# FPGA_Power_Ports.net
KiCad netlist of a schematic drawn in Altium Designer
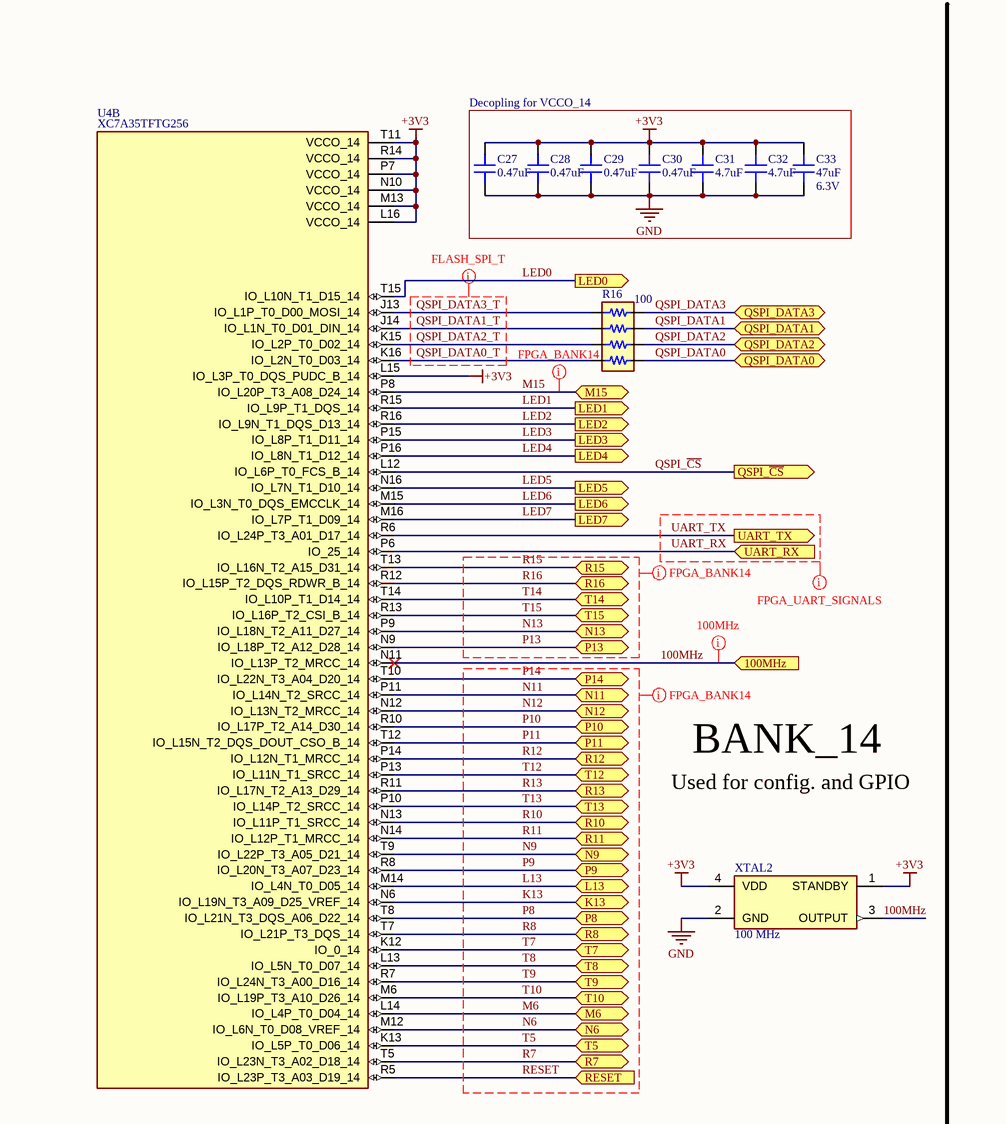
[diagram p0: FPGA_Power&Ports.SchDoc, top left]
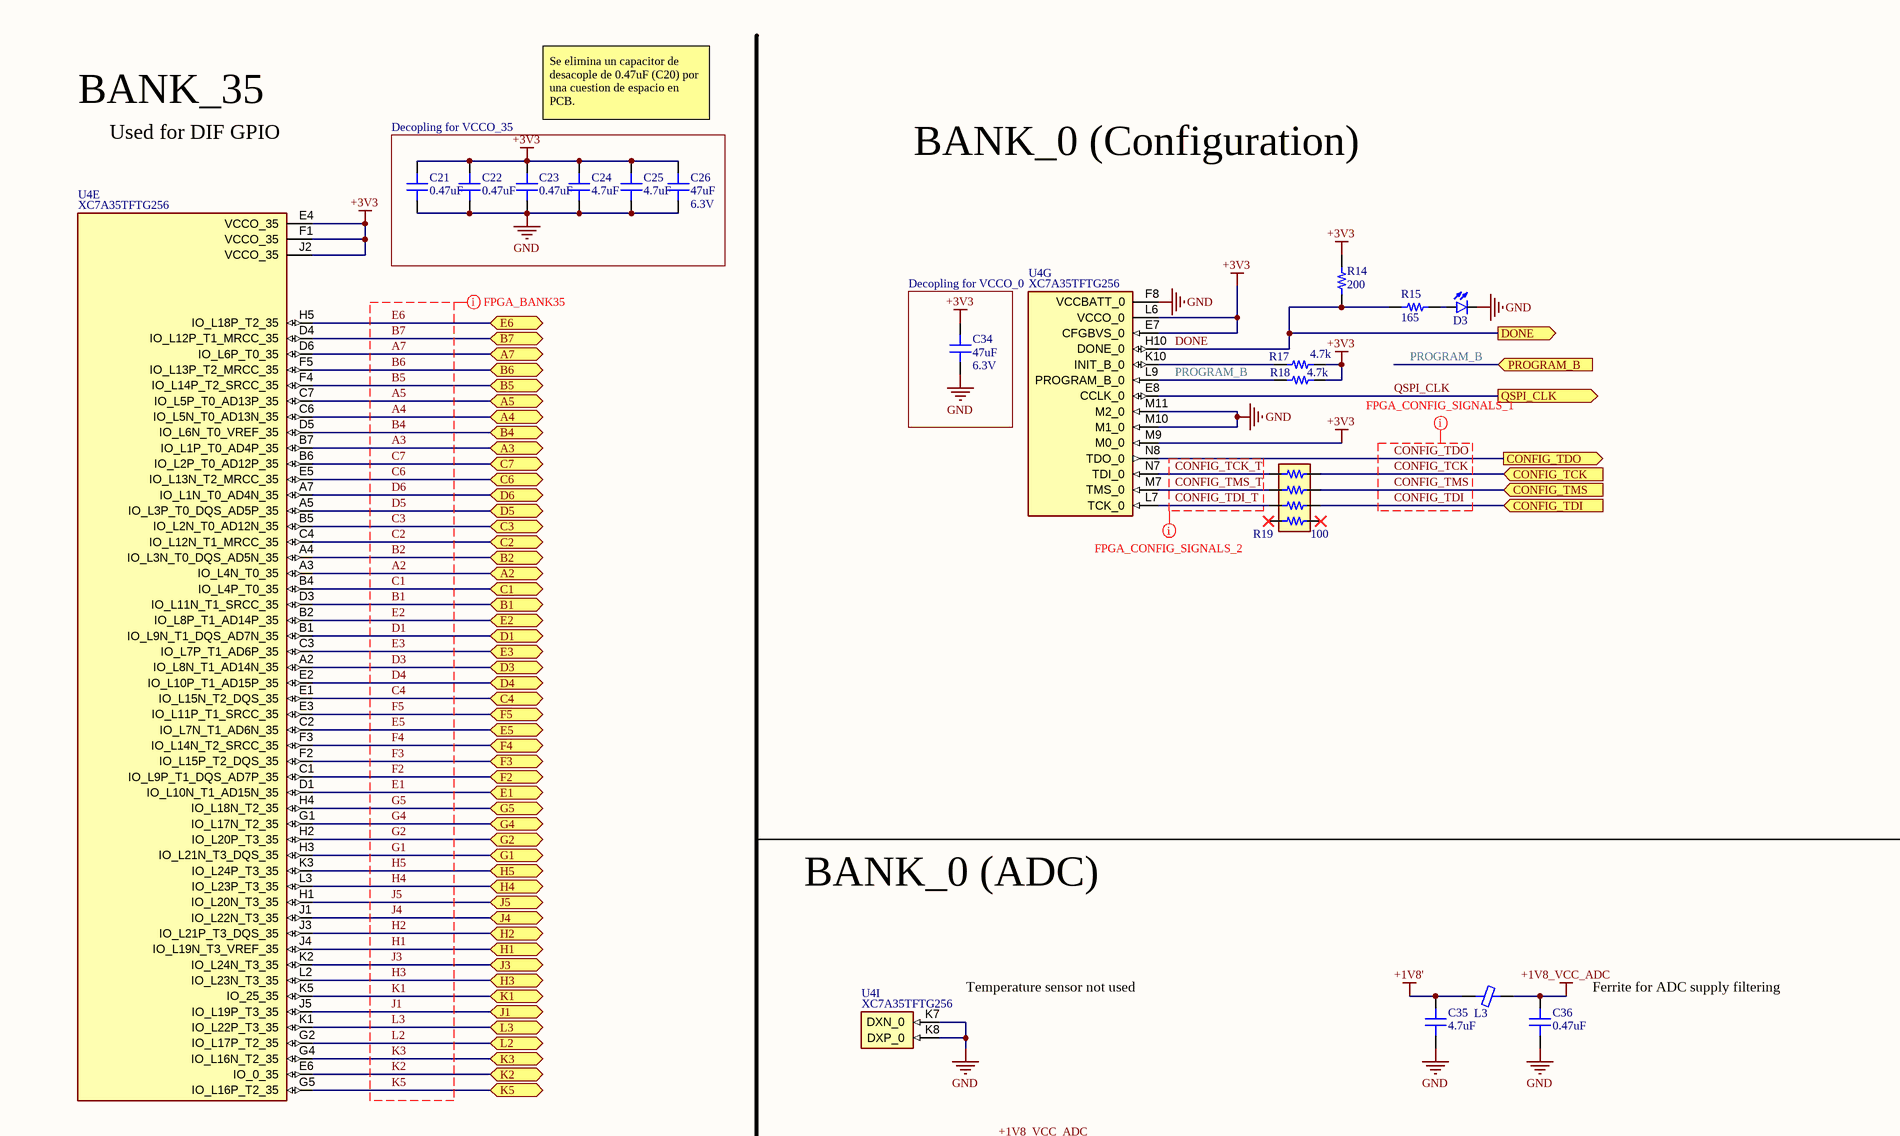
[diagram p1: FPGA_Power&Ports.SchDoc, top right]
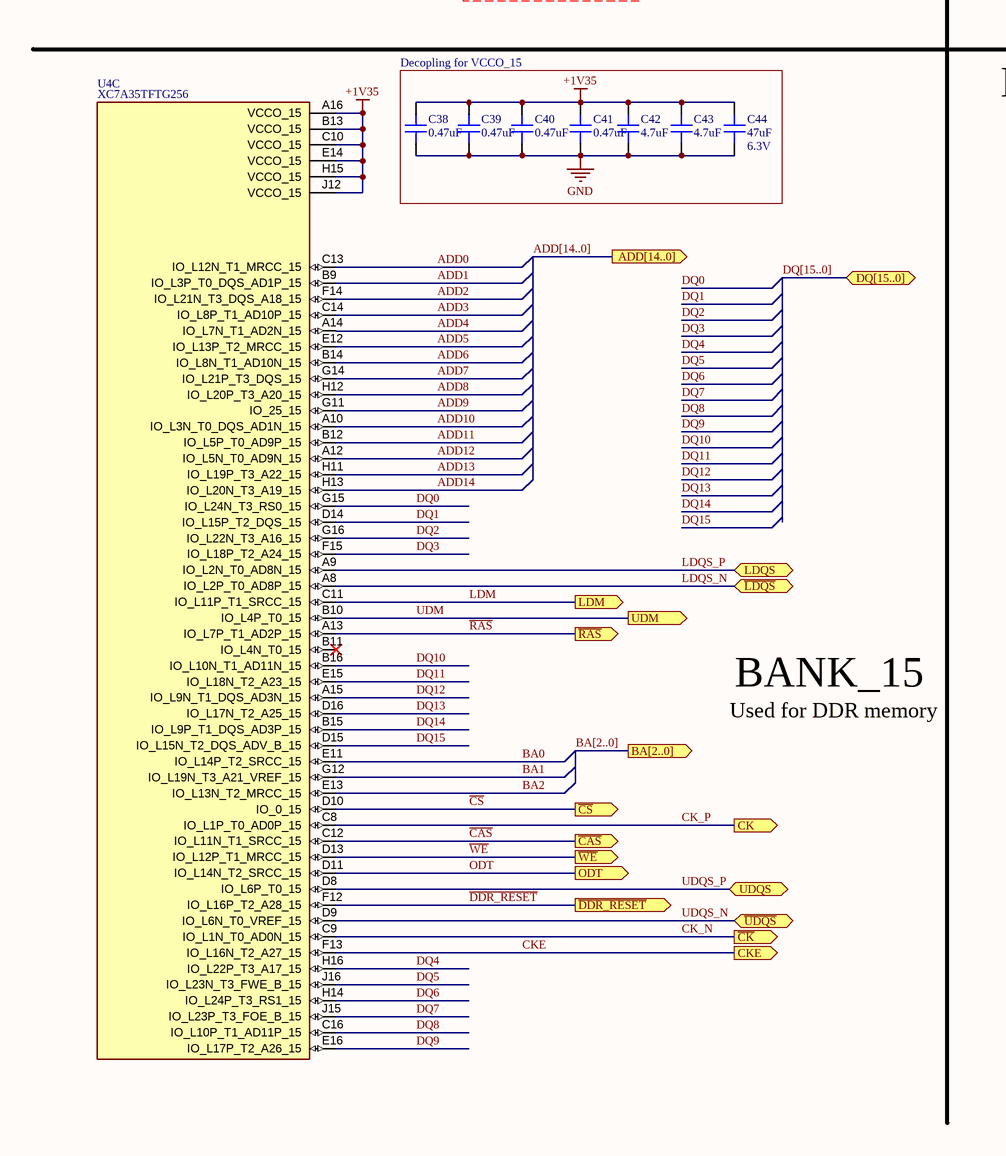
[diagram p2: FPGA_Power&Ports.SchDoc, bottom left]
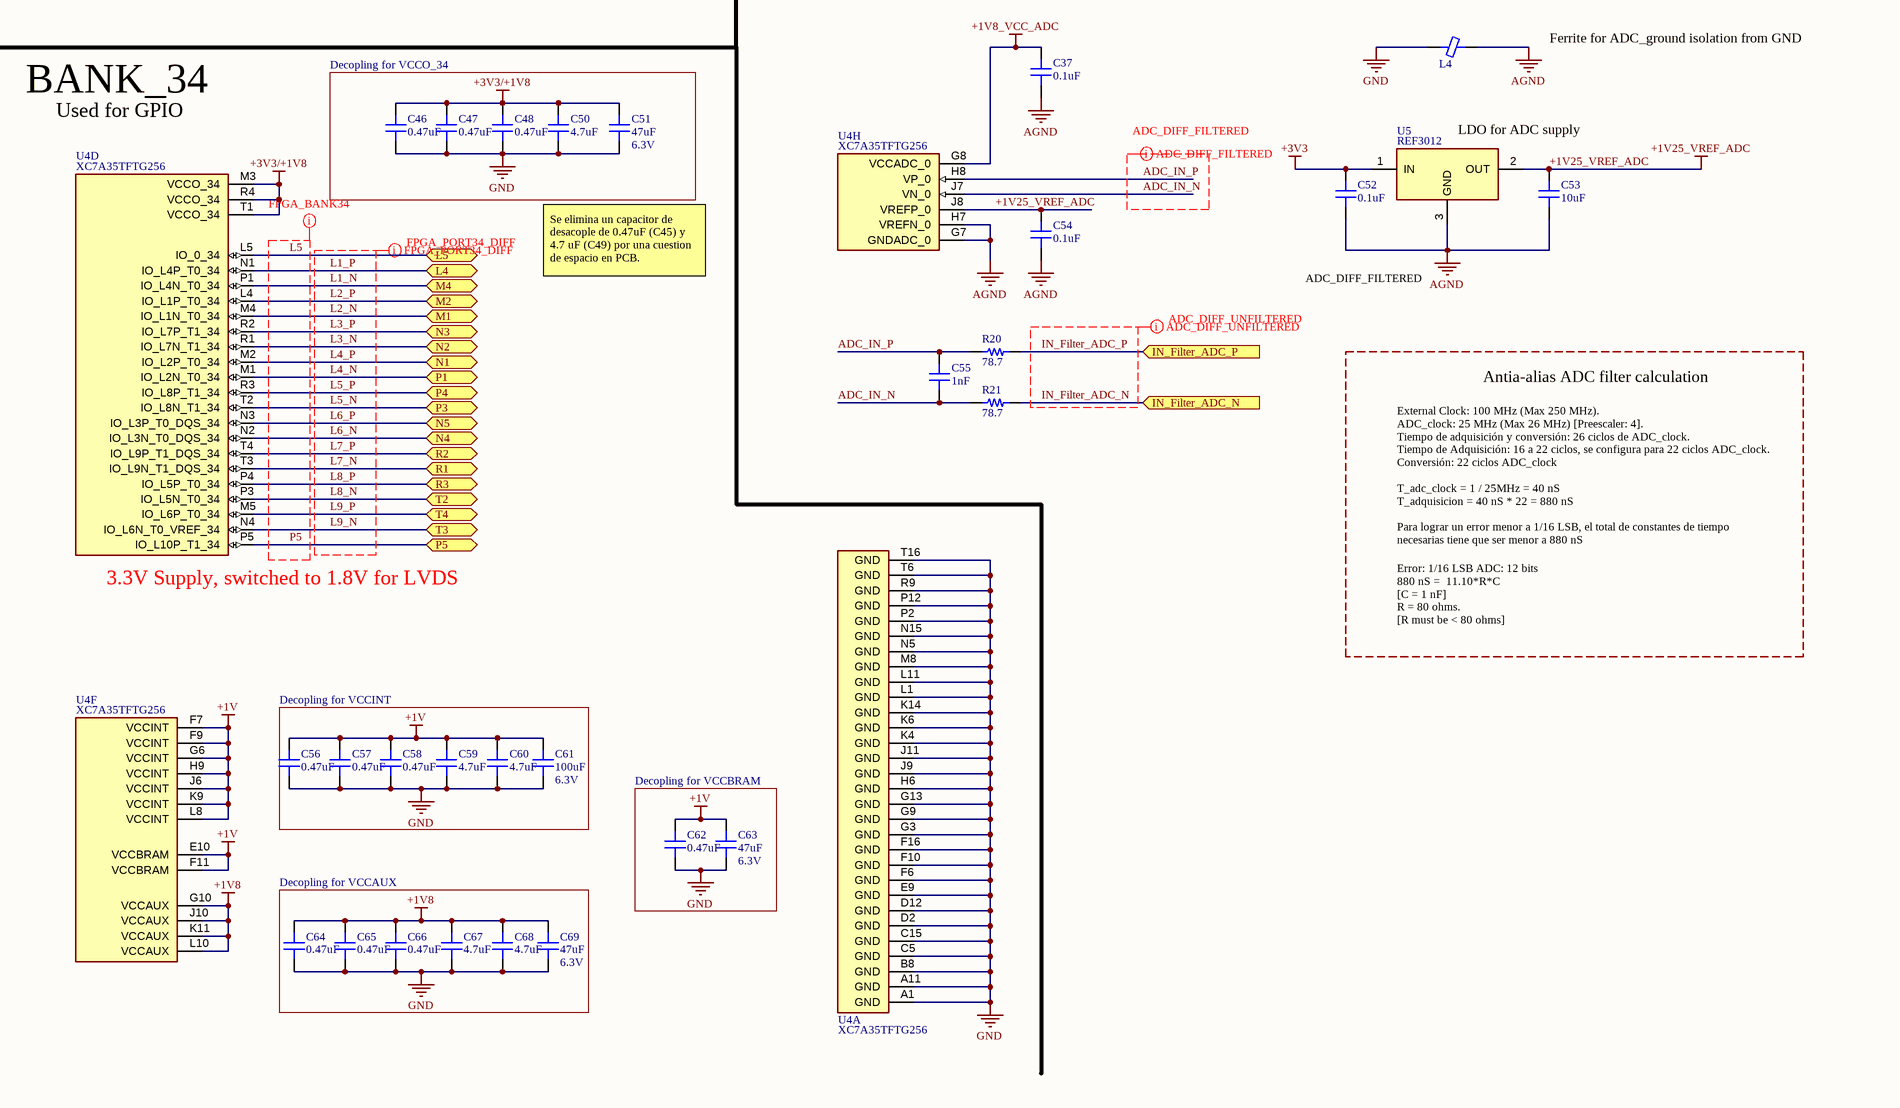
[diagram p3: FPGA_Power&Ports.SchDoc, bottom right]

(export (version "E")
  (design (tool "Eeschema 10.0.6"))
  (components
    (comp (ref "C21")
      (value "0.47uF")
      (footprint "CAP0402")
      (description "CAP CER 0.47uF 10V X7R 0402 10%")
      (fields (field (name "PARTNUMBER") "C0603C474K4RAC") (field (name "TOLERANCE") "10%"))
      (libsource (lib "Pasivos") (part "C0402C474K8RAC"))
    )
    (comp (ref "C22")
      (value "0.47uF")
      (footprint "CAP0402")
      (description "CAP CER 0.47uF 10V X7R 0402 10%")
      (fields (field (name "PARTNUMBER") "C0603C474K4RAC") (field (name "TOLERANCE") "10%"))
      (libsource (lib "Pasivos") (part "C0402C474K8RAC"))
    )
    (comp (ref "C23")
      (value "0.47uF")
      (footprint "CAP0402")
      (description "CAP CER 0.47uF 10V X7R 0402 10%")
      (fields (field (name "PARTNUMBER") "C0603C474K4RAC") (field (name "TOLERANCE") "10%"))
      (libsource (lib "Pasivos") (part "C0402C474K8RAC"))
    )
    (comp (ref "C24")
      (value "4.7uF")
      (footprint "CAP0402")
      (description "CAP CER 4.7uF 6.3V X5R 0402 10%")
      (fields (field (name "PARTNUMBER") "C0402C475M9PAC") (field (name "TOLERANCE") "10%"))
      (libsource (lib "Pasivos") (part "C0402C475M9PAC"))
    )
    (comp (ref "C25")
      (value "4.7uF")
      (footprint "CAP0402")
      (description "CAP CER 4.7uF 6.3V X5R 0402 10%")
      (fields (field (name "PARTNUMBER") "C0402C475M9PAC") (field (name "TOLERANCE") "10%"))
      (libsource (lib "Pasivos") (part "C0402C475M9PAC"))
    )
    (comp (ref "C26")
      (value "47uF")
      (footprint "CAP0805")
      (description "CAP CER 47uF 6.3V X5R 0805 20%")
      (fields
        (field (name "VOLTAGE") "6.3V")
        (field (name "MANUFACTURER") "Samsung")
        (field (name "TOLERANCE") "20%")
      )
      (libsource (lib "Pasivos") (part "CL21A476MQYNNNE"))
    )
    (comp (ref "C27")
      (value "0.47uF")
      (footprint "CAP0402")
      (description "CAP CER 0.47uF 10V X7R 0402 10%")
      (fields (field (name "PARTNUMBER") "C0603C474K4RAC") (field (name "TOLERANCE") "10%"))
      (libsource (lib "Pasivos") (part "C0402C474K8RAC"))
    )
    (comp (ref "C28")
      (value "0.47uF")
      (footprint "CAP0402")
      (description "CAP CER 0.47uF 10V X7R 0402 10%")
      (fields (field (name "PARTNUMBER") "C0603C474K4RAC") (field (name "TOLERANCE") "10%"))
      (libsource (lib "Pasivos") (part "C0402C474K8RAC"))
    )
    (comp (ref "C29")
      (value "0.47uF")
      (footprint "CAP0402")
      (description "CAP CER 0.47uF 10V X7R 0402 10%")
      (fields (field (name "PARTNUMBER") "C0603C474K4RAC") (field (name "TOLERANCE") "10%"))
      (libsource (lib "Pasivos") (part "C0402C474K8RAC"))
    )
    (comp (ref "C30")
      (value "0.47uF")
      (footprint "CAP0402")
      (description "CAP CER 0.47uF 10V X7R 0402 10%")
      (fields (field (name "PARTNUMBER") "C0603C474K4RAC") (field (name "TOLERANCE") "10%"))
      (libsource (lib "Pasivos") (part "C0402C474K8RAC"))
    )
    (comp (ref "C31")
      (value "4.7uF")
      (footprint "CAP0402")
      (description "CAP CER 4.7uF 6.3V X5R 0402 10%")
      (fields (field (name "PARTNUMBER") "C0402C475M9PAC") (field (name "TOLERANCE") "10%"))
      (libsource (lib "Pasivos") (part "C0402C475M9PAC"))
    )
    (comp (ref "C32")
      (value "4.7uF")
      (footprint "CAP0402")
      (description "CAP CER 4.7uF 6.3V X5R 0402 10%")
      (fields (field (name "PARTNUMBER") "C0402C475M9PAC") (field (name "TOLERANCE") "10%"))
      (libsource (lib "Pasivos") (part "C0402C475M9PAC"))
    )
    (comp (ref "C33")
      (value "47uF")
      (footprint "CAP0805")
      (description "CAP CER 47uF 6.3V X5R 0805 20%")
      (fields
        (field (name "VOLTAGE") "6.3V")
        (field (name "MANUFACTURER") "Samsung")
        (field (name "TOLERANCE") "20%")
      )
      (libsource (lib "Pasivos") (part "CL21A476MQYNNNE"))
    )
    (comp (ref "C34")
      (value "47uF")
      (footprint "CAP0805")
      (description "CAP CER 47uF 6.3V X5R 0805 20%")
      (fields
        (field (name "MANUFACTURER") "Samsung")
        (field (name "VOLTAGE") "6.3V")
        (field (name "TOLERANCE") "20%")
      )
      (libsource (lib "Pasivos") (part "CL21A476MQYNNNE"))
    )
    (comp (ref "C35")
      (value "4.7uF")
      (footprint "CAP0402")
      (description "CAP CER 4.7uF 6.3V X5R 0402 10%")
      (fields (field (name "PARTNUMBER") "C0402C475M9PAC") (field (name "TOLERANCE") "10%"))
      (libsource (lib "Pasivos") (part "C0402C475M9PAC"))
    )
    (comp (ref "C36")
      (value "0.47uF")
      (footprint "CAP0402")
      (description "CAP CER 0.47uF 10V X7R 0402 10%")
      (fields (field (name "PARTNUMBER") "C0603C474K4RAC") (field (name "TOLERANCE") "10%"))
      (libsource (lib "Pasivos") (part "C0402C474K8RAC"))
    )
    (comp (ref "C37")
      (value "0.1uF")
      (footprint "CAP0402")
      (description "CAP CER 0.1uF 16V X7R 0402 10%")
      (fields (field (name "TOLERANCE") "10%") (field (name "VOLTAGE") "16V"))
      (libsource (lib "Pasivos") (part "C0402C104K4RAC"))
    )
    (comp (ref "C38")
      (value "0.47uF")
      (footprint "CAP0402")
      (description "CAP CER 0.47uF 10V X7R 0402 10%")
      (fields (field (name "PARTNUMBER") "C0603C474K4RAC") (field (name "TOLERANCE") "10%"))
      (libsource (lib "Pasivos") (part "C0402C474K8RAC"))
    )
    (comp (ref "C39")
      (value "0.47uF")
      (footprint "CAP0402")
      (description "CAP CER 0.47uF 10V X7R 0402 10%")
      (fields (field (name "PARTNUMBER") "C0603C474K4RAC") (field (name "TOLERANCE") "10%"))
      (libsource (lib "Pasivos") (part "C0402C474K8RAC"))
    )
    (comp (ref "C40")
      (value "0.47uF")
      (footprint "CAP0402")
      (description "CAP CER 0.47uF 10V X7R 0402 10%")
      (fields (field (name "PARTNUMBER") "C0603C474K4RAC") (field (name "TOLERANCE") "10%"))
      (libsource (lib "Pasivos") (part "C0402C474K8RAC"))
    )
    (comp (ref "C41")
      (value "0.47uF")
      (footprint "CAP0402")
      (description "CAP CER 0.47uF 10V X7R 0402 10%")
      (fields (field (name "PARTNUMBER") "C0603C474K4RAC") (field (name "TOLERANCE") "10%"))
      (libsource (lib "Pasivos") (part "C0402C474K8RAC"))
    )
    (comp (ref "C42")
      (value "4.7uF")
      (footprint "CAP0402")
      (description "CAP CER 4.7uF 6.3V X5R 0402 10%")
      (fields (field (name "PARTNUMBER") "C0402C475M9PAC") (field (name "TOLERANCE") "10%"))
      (libsource (lib "Pasivos") (part "C0402C475M9PAC"))
    )
    (comp (ref "C43")
      (value "4.7uF")
      (footprint "CAP0402")
      (description "CAP CER 4.7uF 6.3V X5R 0402 10%")
      (fields (field (name "PARTNUMBER") "C0402C475M9PAC") (field (name "TOLERANCE") "10%"))
      (libsource (lib "Pasivos") (part "C0402C475M9PAC"))
    )
    (comp (ref "C44")
      (value "47uF")
      (footprint "CAP0805")
      (description "CAP CER 47uF 6.3V X5R 0805 20%")
      (fields
        (field (name "VOLTAGE") "6.3V")
        (field (name "MANUFACTURER") "Samsung")
        (field (name "TOLERANCE") "20%")
      )
      (libsource (lib "Pasivos") (part "CL21A476MQYNNNE"))
    )
    (comp (ref "C46")
      (value "0.47uF")
      (footprint "CAP0402")
      (description "CAP CER 0.47uF 10V X7R 0402 10%")
      (fields (field (name "PARTNUMBER") "C0603C474K4RAC") (field (name "TOLERANCE") "10%"))
      (libsource (lib "Pasivos") (part "C0402C474K8RAC"))
    )
    (comp (ref "C47")
      (value "0.47uF")
      (footprint "CAP0402")
      (description "CAP CER 0.47uF 10V X7R 0402 10%")
      (fields (field (name "PARTNUMBER") "C0603C474K4RAC") (field (name "TOLERANCE") "10%"))
      (libsource (lib "Pasivos") (part "C0402C474K8RAC"))
    )
    (comp (ref "C48")
      (value "0.47uF")
      (footprint "CAP0402")
      (description "CAP CER 0.47uF 10V X7R 0402 10%")
      (fields (field (name "PARTNUMBER") "C0603C474K4RAC") (field (name "TOLERANCE") "10%"))
      (libsource (lib "Pasivos") (part "C0402C474K8RAC"))
    )
    (comp (ref "C50")
      (value "4.7uF")
      (footprint "CAP0402")
      (description "CAP CER 4.7uF 6.3V X5R 0402 10%")
      (fields (field (name "PARTNUMBER") "C0402C475M9PAC") (field (name "TOLERANCE") "10%"))
      (libsource (lib "Pasivos") (part "C0402C475M9PAC"))
    )
    (comp (ref "C51")
      (value "47uF")
      (footprint "CAP0805")
      (description "CAP CER 47uF 6.3V X5R 0805 20%")
      (fields
        (field (name "VOLTAGE") "6.3V")
        (field (name "MANUFACTURER") "Samsung")
        (field (name "TOLERANCE") "20%")
      )
      (libsource (lib "Pasivos") (part "CL21A476MQYNNNE"))
    )
    (comp (ref "C52")
      (value "0.1uF")
      (footprint "CAP0402")
      (description "CAP CER 0.1uF 16V X7R 0402 10%")
      (fields (field (name "TOLERANCE") "10%") (field (name "VOLTAGE") "16V"))
      (libsource (lib "Pasivos") (part "C0402C104K4RAC"))
    )
    (comp (ref "C53")
      (value "10uF")
      (footprint "CAP0402")
      (description "CAP CER 10uF 6.3V X5R 0402 10%")
      (fields (field (name "TOLERANCE") "10%") (field (name "MANUFACTURER") "Kemet"))
      (libsource (lib "Pasivos") (part "C0402C106M9PAC"))
    )
    (comp (ref "C54")
      (value "0.1uF")
      (footprint "CAP0402")
      (description "CAP CER 0.1uF 16V X7R 0402 10%")
      (fields (field (name "TOLERANCE") "10%") (field (name "VOLTAGE") "16V"))
      (libsource (lib "Pasivos") (part "C0402C104K4RAC"))
    )
    (comp (ref "C55")
      (value "1nF")
      (footprint "CAP0402")
      (description "CAP CER 1nF 16V X7R 0402 10%")
      (fields (field (name "TOLERANCE") "10%") (field (name "PARTNUMBER") "C0402C102K4RAC"))
      (libsource (lib "Pasivos") (part "C0402C102K4RAC"))
    )
    (comp (ref "C56")
      (value "0.47uF")
      (footprint "CAP0402")
      (description "CAP CER 0.47uF 10V X7R 0402 10%")
      (fields (field (name "PARTNUMBER") "C0603C474K4RAC") (field (name "TOLERANCE") "10%"))
      (libsource (lib "Pasivos") (part "C0402C474K8RAC"))
    )
    (comp (ref "C57")
      (value "0.47uF")
      (footprint "CAP0402")
      (description "CAP CER 0.47uF 10V X7R 0402 10%")
      (fields (field (name "PARTNUMBER") "C0603C474K4RAC") (field (name "TOLERANCE") "10%"))
      (libsource (lib "Pasivos") (part "C0402C474K8RAC"))
    )
    (comp (ref "C58")
      (value "0.47uF")
      (footprint "CAP0402")
      (description "CAP CER 0.47uF 10V X7R 0402 10%")
      (fields (field (name "PARTNUMBER") "C0603C474K4RAC") (field (name "TOLERANCE") "10%"))
      (libsource (lib "Pasivos") (part "C0402C474K8RAC"))
    )
    (comp (ref "C59")
      (value "4.7uF")
      (footprint "CAP0402")
      (description "CAP CER 4.7uF 6.3V X5R 0402 10%")
      (fields (field (name "PARTNUMBER") "C0402C475M9PAC") (field (name "TOLERANCE") "10%"))
      (libsource (lib "Pasivos") (part "C0402C475M9PAC"))
    )
    (comp (ref "C60")
      (value "4.7uF")
      (footprint "CAP0402")
      (description "CAP CER 4.7uF 6.3V X5R 0402 10%")
      (fields (field (name "PARTNUMBER") "C0402C475M9PAC") (field (name "TOLERANCE") "10%"))
      (libsource (lib "Pasivos") (part "C0402C475M9PAC"))
    )
    (comp (ref "C61")
      (value "100uF")
      (footprint "CAP1206")
      (description "CAP CER 100uF 6.3V X5R 1206 20%")
      (fields
        (field (name "PARTNUMBER") "C1206C107M9PAC")
        (field (name "TOLERANCE") "20%")
        (field (name "VOLTAGE") "6.3V")
      )
      (libsource (lib "Pasivos") (part "C1206C107M9PAC"))
    )
    (comp (ref "C62")
      (value "0.47uF")
      (footprint "CAP0402")
      (description "CAP CER 0.47uF 10V X7R 0402 10%")
      (fields (field (name "PARTNUMBER") "C0603C474K4RAC") (field (name "TOLERANCE") "10%"))
      (libsource (lib "Pasivos") (part "C0402C474K8RAC"))
    )
    (comp (ref "C63")
      (value "47uF")
      (footprint "CAP0805")
      (description "CAP CER 47uF 6.3V X5R 0805 20%")
      (fields
        (field (name "VOLTAGE") "6.3V")
        (field (name "MANUFACTURER") "Samsung")
        (field (name "TOLERANCE") "20%")
      )
      (libsource (lib "Pasivos") (part "CL21A476MQYNNNE"))
    )
    (comp (ref "C64")
      (value "0.47uF")
      (footprint "CAP0402")
      (description "CAP CER 0.47uF 10V X7R 0402 10%")
      (fields (field (name "PARTNUMBER") "C0603C474K4RAC") (field (name "TOLERANCE") "10%"))
      (libsource (lib "Pasivos") (part "C0402C474K8RAC"))
    )
    (comp (ref "C65")
      (value "0.47uF")
      (footprint "CAP0402")
      (description "CAP CER 0.47uF 10V X7R 0402 10%")
      (fields (field (name "PARTNUMBER") "C0603C474K4RAC") (field (name "TOLERANCE") "10%"))
      (libsource (lib "Pasivos") (part "C0402C474K8RAC"))
    )
    (comp (ref "C66")
      (value "0.47uF")
      (footprint "CAP0402")
      (description "CAP CER 0.47uF 10V X7R 0402 10%")
      (fields (field (name "PARTNUMBER") "C0603C474K4RAC") (field (name "TOLERANCE") "10%"))
      (libsource (lib "Pasivos") (part "C0402C474K8RAC"))
    )
    (comp (ref "C67")
      (value "4.7uF")
      (footprint "CAP0402")
      (description "CAP CER 4.7uF 6.3V X5R 0402 10%")
      (fields (field (name "PARTNUMBER") "C0402C475M9PAC") (field (name "TOLERANCE") "10%"))
      (libsource (lib "Pasivos") (part "C0402C475M9PAC"))
    )
    (comp (ref "C68")
      (value "4.7uF")
      (footprint "CAP0402")
      (description "CAP CER 4.7uF 6.3V X5R 0402 10%")
      (fields (field (name "PARTNUMBER") "C0402C475M9PAC") (field (name "TOLERANCE") "10%"))
      (libsource (lib "Pasivos") (part "C0402C475M9PAC"))
    )
    (comp (ref "C69")
      (value "47uF")
      (footprint "CAP0805")
      (description "CAP CER 47uF 6.3V X5R 0805 20%")
      (fields
        (field (name "VOLTAGE") "6.3V")
        (field (name "MANUFACTURER") "Samsung")
        (field (name "TOLERANCE") "20%")
      )
      (libsource (lib "Pasivos") (part "CL21A476MQYNNNE"))
    )
    (comp (ref "D3")
      (value "597-3305-607F")
      (footprint "0603_LED")
      (description "LED blue diffused 0603 SMD")
      (libsource (lib "Integrated_Circuits") (part "LED_BLUE_0603"))
    )
    (comp (ref "L3")
      (value "HZ0603C651R-10")
      (footprint "Fer0603")
      (description "FERRITE BEAD 650 OHM 0603 1LN 0603")
      (libsource (lib "Pasivos") (part "HZ0603C651R-10"))
    )
    (comp (ref "L4")
      (value "HZ0603C651R-10")
      (footprint "Fer0603")
      (description "FERRITE BEAD 650 OHM 0603 1LN 0603")
      (libsource (lib "Pasivos") (part "HZ0603C651R-10"))
    )
    (comp (ref "R14")
      (value "200")
      (footprint "RES0402")
      (description "RES SMD 200 OHM 1% 0.063W 0402")
      (fields (field (name "POWER") "0.063W") (field (name "MANUFACTURER") "Vishay"))
      (libsource (lib "Pasivos") (part "CRCW0402200RFK"))
    )
    (comp (ref "R15")
      (value "165")
      (footprint "RES0402")
      (description "RES SMD 165 OHM 1% 0.063W 0402")
      (fields (field (name "MANUFACTURER") "Vishay") (field (name "TOLERANCE") "1%"))
      (libsource (lib "Pasivos") (part "CRCW0402165RFK"))
    )
    (comp (ref "R16")
      (value "100")
      (footprint "ArrayResistor-1206")
      (description "RES ARRAY 4 RES 100 OHM 1206")
      (libsource (lib "Pasivos") (part "EXB-38V101JV"))
    )
    (comp (ref "R17")
      (value "4.7k")
      (footprint "RES0402")
      (description "RES SMD 4.7K OHM 1% 0.063W 0402")
      (fields (field (name "POWER") "0.063 W") (field (name "MANUFACTURER") "Vishay"))
      (libsource (lib "Pasivos") (part "CRCW04024K70FK"))
    )
    (comp (ref "R18")
      (value "4.7k")
      (footprint "RES0402")
      (description "RES SMD 4.7K OHM 1% 0.063W 0402")
      (fields (field (name "POWER") "0.063 W") (field (name "MANUFACTURER") "Vishay"))
      (libsource (lib "Pasivos") (part "CRCW04024K70FK"))
    )
    (comp (ref "R19")
      (value "100")
      (footprint "ArrayResistor-1206")
      (description "RES ARRAY 4 RES 100 OHM 1206")
      (libsource (lib "Pasivos") (part "EXB-38V101JV"))
    )
    (comp (ref "R20")
      (value "78.7")
      (footprint "RES0402")
      (description "RES SMD 78.7 OHM 1% 0.063W 0402")
      (fields (field (name "MANUFACTURER") "Vishay") (field (name "TOLERANCE") "1%"))
      (libsource (lib "Pasivos") (part "CRCW040278R7FK"))
    )
    (comp (ref "R21")
      (value "78.7")
      (footprint "RES0402")
      (description "RES SMD 78.7 OHM 1% 0.063W 0402")
      (fields (field (name "MANUFACTURER") "Vishay") (field (name "TOLERANCE") "1%"))
      (libsource (lib "Pasivos") (part "CRCW040278R7FK"))
    )
    (comp (ref "U4")
      (value "XC7A35TFTG256")
      (footprint "BGA-256")
      (description "FPGA")
      (libsource (lib "Integrated_Circuits") (part "XC7A35TFTG256"))
    )
    (comp (ref "U5")
      (value "REF3012")
      (footprint "SOT23-3")
      (description "Voltage Reference 1,5V")
      (libsource (lib "Integrated_Circuits") (part "REF3012"))
    )
    (comp (ref "XTAL2")
      (value "ASFLMB-100.000MHZ-LC-T")
      (footprint "XTAL_ASFLMB")
      (description "Crystal 100 MHz")
      (fields (field (name "MANUFACTURER") "Abracom") (field (name "FREQUENCY") "100 MHz"))
      (libsource (lib "Integrated_Circuits") (part "XTAL_100MHz"))
    )
  )
  (nets
    (net (code "1") (name "+1V") (class "Default")
      (node (ref "C56") (pin "2") (pinfunction "2_2") (pintype "passive"))
      (node (ref "C57") (pin "2") (pinfunction "2_2") (pintype "passive"))
      (node (ref "C58") (pin "2") (pinfunction "2_2") (pintype "passive"))
      (node (ref "C59") (pin "2") (pinfunction "2_2") (pintype "passive"))
      (node (ref "C60") (pin "2") (pinfunction "2_2") (pintype "passive"))
      (node (ref "C61") (pin "2") (pinfunction "2_2") (pintype "passive"))
      (node (ref "C62") (pin "2") (pinfunction "2_2") (pintype "passive"))
      (node (ref "C63") (pin "2") (pinfunction "2_2") (pintype "passive"))
      (node (ref "U4") (pin "E10") (pinfunction "VCCBRAM_E10") (pintype "power_in"))
      (node (ref "U4") (pin "F11") (pinfunction "VCCBRAM_F11") (pintype "power_in"))
      (node (ref "U4") (pin "F7") (pinfunction "VCCINT_F7") (pintype "power_in"))
      (node (ref "U4") (pin "F9") (pinfunction "VCCINT_F9") (pintype "power_in"))
      (node (ref "U4") (pin "G6") (pinfunction "VCCINT_G6") (pintype "power_in"))
      (node (ref "U4") (pin "H9") (pinfunction "VCCINT_H9") (pintype "power_in"))
      (node (ref "U4") (pin "J6") (pinfunction "VCCINT_J6") (pintype "power_in"))
      (node (ref "U4") (pin "K9") (pinfunction "VCCINT_K9") (pintype "power_in"))
      (node (ref "U4") (pin "L8") (pinfunction "VCCINT_L8") (pintype "power_in"))
    )
    (net (code "2") (name "+1V8") (class "Default")
      (node (ref "C64") (pin "2") (pinfunction "2_2") (pintype "passive"))
      (node (ref "C65") (pin "2") (pinfunction "2_2") (pintype "passive"))
      (node (ref "C66") (pin "2") (pinfunction "2_2") (pintype "passive"))
      (node (ref "C67") (pin "2") (pinfunction "2_2") (pintype "passive"))
      (node (ref "C68") (pin "2") (pinfunction "2_2") (pintype "passive"))
      (node (ref "C69") (pin "2") (pinfunction "2_2") (pintype "passive"))
      (node (ref "U4") (pin "G10") (pinfunction "VCCAUX_G10") (pintype "power_in"))
      (node (ref "U4") (pin "J10") (pinfunction "VCCAUX_J10") (pintype "power_in"))
      (node (ref "U4") (pin "K11") (pinfunction "VCCAUX_K11") (pintype "power_in"))
      (node (ref "U4") (pin "L10") (pinfunction "VCCAUX_L10") (pintype "power_in"))
    )
    (net (code "3") (name "+1V8'") (class "Default")
      (node (ref "C35") (pin "2") (pinfunction "2_2") (pintype "passive"))
      (node (ref "L3") (pin "1") (pinfunction "1_1") (pintype "passive"))
    )
    (net (code "4") (name "+1V8_VCC_ADC") (class "Default")
      (node (ref "C36") (pin "2") (pinfunction "2_2") (pintype "passive"))
      (node (ref "C37") (pin "2") (pinfunction "2_2") (pintype "passive"))
      (node (ref "L3") (pin "2") (pinfunction "2_2") (pintype "passive"))
      (node (ref "U4") (pin "G8") (pinfunction "VCCADC_0_G8") (pintype "power_in"))
    )
    (net (code "5") (name "+1V25_VREF_ADC") (class "Default")
      (node (ref "C53") (pin "2") (pinfunction "2_2") (pintype "passive"))
      (node (ref "C54") (pin "2") (pinfunction "2_2") (pintype "passive"))
      (node (ref "U4") (pin "J8") (pinfunction "VREFP_0_J8") (pintype "power_in"))
      (node (ref "U5") (pin "2") (pinfunction "OUT_2") (pintype "power_in"))
    )
    (net (code "6") (name "+1V35") (class "Default")
      (node (ref "C38") (pin "2") (pinfunction "2_2") (pintype "passive"))
      (node (ref "C39") (pin "2") (pinfunction "2_2") (pintype "passive"))
      (node (ref "C40") (pin "2") (pinfunction "2_2") (pintype "passive"))
      (node (ref "C41") (pin "2") (pinfunction "2_2") (pintype "passive"))
      (node (ref "C42") (pin "2") (pinfunction "2_2") (pintype "passive"))
      (node (ref "C43") (pin "2") (pinfunction "2_2") (pintype "passive"))
      (node (ref "C44") (pin "2") (pinfunction "2_2") (pintype "passive"))
      (node (ref "U4") (pin "A16") (pinfunction "VCCO_15_A16") (pintype "power_in"))
      (node (ref "U4") (pin "B13") (pinfunction "VCCO_15_B13") (pintype "power_in"))
      (node (ref "U4") (pin "C10") (pinfunction "VCCO_15_C10") (pintype "power_in"))
      (node (ref "U4") (pin "E14") (pinfunction "VCCO_15_E14") (pintype "power_in"))
      (node (ref "U4") (pin "H15") (pinfunction "VCCO_15_H15") (pintype "power_in"))
      (node (ref "U4") (pin "J12") (pinfunction "VCCO_15_J12") (pintype "power_in"))
    )
    (net (code "7") (name "+3V3") (class "Default")
      (node (ref "C21") (pin "2") (pinfunction "2_2") (pintype "passive"))
      (node (ref "C22") (pin "2") (pinfunction "2_2") (pintype "passive"))
      (node (ref "C23") (pin "2") (pinfunction "2_2") (pintype "passive"))
      (node (ref "C24") (pin "2") (pinfunction "2_2") (pintype "passive"))
      (node (ref "C25") (pin "2") (pinfunction "2_2") (pintype "passive"))
      (node (ref "C26") (pin "2") (pinfunction "2_2") (pintype "passive"))
      (node (ref "C27") (pin "2") (pinfunction "2_2") (pintype "passive"))
      (node (ref "C28") (pin "2") (pinfunction "2_2") (pintype "passive"))
      (node (ref "C29") (pin "2") (pinfunction "2_2") (pintype "passive"))
      (node (ref "C30") (pin "2") (pinfunction "2_2") (pintype "passive"))
      (node (ref "C31") (pin "2") (pinfunction "2_2") (pintype "passive"))
      (node (ref "C32") (pin "2") (pinfunction "2_2") (pintype "passive"))
      (node (ref "C33") (pin "2") (pinfunction "2_2") (pintype "passive"))
      (node (ref "C34") (pin "2") (pinfunction "2_2") (pintype "passive"))
      (node (ref "C52") (pin "2") (pinfunction "2_2") (pintype "passive"))
      (node (ref "R14") (pin "2") (pinfunction "2_2") (pintype "passive"))
      (node (ref "R17") (pin "2") (pinfunction "2_2") (pintype "passive"))
      (node (ref "R18") (pin "2") (pinfunction "2_2") (pintype "passive"))
      (node (ref "U4") (pin "E4") (pinfunction "VCCO_35_E4") (pintype "power_in"))
      (node (ref "U4") (pin "E7") (pinfunction "CFGBVS_0_E7") (pintype "input"))
      (node (ref "U4") (pin "F1") (pinfunction "VCCO_35_F1") (pintype "power_in"))
      (node (ref "U4") (pin "J2") (pinfunction "VCCO_35_J2") (pintype "power_in"))
      (node (ref "U4") (pin "L15") (pinfunction "IO_L3P_T0_DQS_PUDC_B_14_L15") (pintype "bidirectional"))
      (node (ref "U4") (pin "L16") (pinfunction "VCCO_14_L16") (pintype "power_in"))
      (node (ref "U4") (pin "L6") (pinfunction "VCCO_0_L6") (pintype "power_in"))
      (node (ref "U4") (pin "M13") (pinfunction "VCCO_14_M13") (pintype "power_in"))
      (node (ref "U4") (pin "M9") (pinfunction "M0_0_M9") (pintype "input"))
      (node (ref "U4") (pin "N10") (pinfunction "VCCO_14_N10") (pintype "power_in"))
      (node (ref "U4") (pin "P7") (pinfunction "VCCO_14_P7") (pintype "power_in"))
      (node (ref "U4") (pin "R14") (pinfunction "VCCO_14_R14") (pintype "power_in"))
      (node (ref "U4") (pin "T11") (pinfunction "VCCO_14_T11") (pintype "power_in"))
      (node (ref "U5") (pin "1") (pinfunction "IN_1") (pintype "power_in"))
      (node (ref "XTAL2") (pin "1") (pinfunction "STANDBY_1") (pintype "passive"))
      (node (ref "XTAL2") (pin "4") (pinfunction "VDD_4") (pintype "power_in"))
    )
    (net (code "8") (name "+3V3{slash}+1V8") (class "Default")
      (node (ref "C46") (pin "2") (pinfunction "2_2") (pintype "passive"))
      (node (ref "C47") (pin "2") (pinfunction "2_2") (pintype "passive"))
      (node (ref "C48") (pin "2") (pinfunction "2_2") (pintype "passive"))
      (node (ref "C50") (pin "2") (pinfunction "2_2") (pintype "passive"))
      (node (ref "C51") (pin "2") (pinfunction "2_2") (pintype "passive"))
      (node (ref "U4") (pin "M3") (pinfunction "VCCO_34_M3") (pintype "power_in"))
      (node (ref "U4") (pin "R4") (pinfunction "VCCO_34_R4") (pintype "power_in"))
      (node (ref "U4") (pin "T1") (pinfunction "VCCO_34_T1") (pintype "power_in"))
    )
    (net (code "9") (name "/100MHz") (class "Default")
      (node (ref "U4") (pin "N11") (pinfunction "IO_L13P_T2_MRCC_14_N11") (pintype "bidirectional"))
      (node (ref "XTAL2") (pin "3") (pinfunction "OUTPUT_3") (pintype "output"))
    )
    (net (code "10") (name "/A2") (class "Default")
      (node (ref "U4") (pin "A3") (pinfunction "IO_L4N_T0_35_A3") (pintype "bidirectional"))
    )
    (net (code "11") (name "/A3") (class "Default")
      (node (ref "U4") (pin "B7") (pinfunction "IO_L1P_T0_AD4P_35_B7") (pintype "bidirectional"))
    )
    (net (code "12") (name "/A4") (class "Default")
      (node (ref "U4") (pin "C6") (pinfunction "IO_L5N_T0_AD13N_35_C6") (pintype "bidirectional"))
    )
    (net (code "13") (name "/A5") (class "Default")
      (node (ref "U4") (pin "C7") (pinfunction "IO_L5P_T0_AD13P_35_C7") (pintype "bidirectional"))
    )
    (net (code "14") (name "/A7") (class "Default")
      (node (ref "U4") (pin "D6") (pinfunction "IO_L6P_T0_35_D6") (pintype "bidirectional"))
    )
    (net (code "15") (name "/ADC_IN_N") (class "Default")
      (node (ref "C55") (pin "1") (pinfunction "1_1") (pintype "passive"))
      (node (ref "R21") (pin "1") (pinfunction "1_1") (pintype "passive"))
      (node (ref "U4") (pin "J7") (pinfunction "VN_0_J7") (pintype "input"))
    )
    (net (code "16") (name "/ADC_IN_P") (class "Default")
      (node (ref "C55") (pin "2") (pinfunction "2_2") (pintype "passive"))
      (node (ref "R20") (pin "1") (pinfunction "1_1") (pintype "passive"))
      (node (ref "U4") (pin "H8") (pinfunction "VP_0_H8") (pintype "input"))
    )
    (net (code "17") (name "/ADD0") (class "Default")
      (node (ref "U4") (pin "C13") (pinfunction "IO_L12N_T1_MRCC_15_C13") (pintype "bidirectional"))
    )
    (net (code "18") (name "/ADD1") (class "Default")
      (node (ref "U4") (pin "B9") (pinfunction "IO_L3P_T0_DQS_AD1P_15_B9") (pintype "bidirectional"))
    )
    (net (code "19") (name "/ADD2") (class "Default")
      (node (ref "U4") (pin "F14") (pinfunction "IO_L21N_T3_DQS_A18_15_F14") (pintype "bidirectional"))
    )
    (net (code "20") (name "/ADD3") (class "Default")
      (node (ref "U4") (pin "C14") (pinfunction "IO_L8P_T1_AD10P_15_C14") (pintype "bidirectional"))
    )
    (net (code "21") (name "/ADD4") (class "Default")
      (node (ref "U4") (pin "A14") (pinfunction "IO_L7N_T1_AD2N_15_A14") (pintype "bidirectional"))
    )
    (net (code "22") (name "/ADD5") (class "Default")
      (node (ref "U4") (pin "E12") (pinfunction "IO_L13P_T2_MRCC_15_E12") (pintype "bidirectional"))
    )
    (net (code "23") (name "/ADD6") (class "Default")
      (node (ref "U4") (pin "B14") (pinfunction "IO_L8N_T1_AD10N_15_B14") (pintype "bidirectional"))
    )
    (net (code "24") (name "/ADD7") (class "Default")
      (node (ref "U4") (pin "G14") (pinfunction "IO_L21P_T3_DQS_15_G14") (pintype "bidirectional"))
    )
    (net (code "25") (name "/ADD8") (class "Default")
      (node (ref "U4") (pin "H12") (pinfunction "IO_L20P_T3_A20_15_H12") (pintype "bidirectional"))
    )
    (net (code "26") (name "/ADD9") (class "Default")
      (node (ref "U4") (pin "G11") (pinfunction "IO_25_15_G11") (pintype "bidirectional"))
    )
    (net (code "27") (name "/ADD10") (class "Default")
      (node (ref "U4") (pin "A10") (pinfunction "IO_L3N_T0_DQS_AD1N_15_A10") (pintype "bidirectional"))
    )
    (net (code "28") (name "/ADD11") (class "Default")
      (node (ref "U4") (pin "B12") (pinfunction "IO_L5P_T0_AD9P_15_B12") (pintype "bidirectional"))
    )
    (net (code "29") (name "/ADD12") (class "Default")
      (node (ref "U4") (pin "A12") (pinfunction "IO_L5N_T0_AD9N_15_A12") (pintype "bidirectional"))
    )
    (net (code "30") (name "/ADD13") (class "Default")
      (node (ref "U4") (pin "H11") (pinfunction "IO_L19P_T3_A22_15_H11") (pintype "bidirectional"))
    )
    (net (code "31") (name "/ADD14") (class "Default")
      (node (ref "U4") (pin "H13") (pinfunction "IO_L20N_T3_A19_15_H13") (pintype "bidirectional"))
    )
    (net (code "33") (name "/B1") (class "Default")
      (node (ref "U4") (pin "D3") (pinfunction "IO_L11N_T1_SRCC_35_D3") (pintype "bidirectional"))
    )
    (net (code "34") (name "/B2") (class "Default")
      (node (ref "U4") (pin "A4") (pinfunction "IO_L3N_T0_DQS_AD5N_35_A4") (pintype "bidirectional"))
    )
    (net (code "35") (name "/B4") (class "Default")
      (node (ref "U4") (pin "D5") (pinfunction "IO_L6N_T0_VREF_35_D5") (pintype "bidirectional"))
    )
    (net (code "36") (name "/B5") (class "Default")
      (node (ref "U4") (pin "F4") (pinfunction "IO_L14P_T2_SRCC_35_F4") (pintype "bidirectional"))
    )
    (net (code "37") (name "/B6") (class "Default")
      (node (ref "U4") (pin "F5") (pinfunction "IO_L13P_T2_MRCC_35_F5") (pintype "bidirectional"))
    )
    (net (code "38") (name "/B7") (class "Default")
      (node (ref "U4") (pin "D4") (pinfunction "IO_L12P_T1_MRCC_35_D4") (pintype "bidirectional"))
    )
    (net (code "39") (name "/BA0") (class "Default")
      (node (ref "U4") (pin "E11") (pinfunction "IO_L14P_T2_SRCC_15_E11") (pintype "bidirectional"))
    )
    (net (code "40") (name "/BA1") (class "Default")
      (node (ref "U4") (pin "G12") (pinfunction "IO_L19N_T3_A21_VREF_15_G12") (pintype "bidirectional"))
    )
    (net (code "41") (name "/BA2") (class "Default")
      (node (ref "U4") (pin "E13") (pinfunction "IO_L13N_T2_MRCC_15_E13") (pintype "bidirectional"))
    )
    (net (code "43") (name "/C1") (class "Default")
      (node (ref "U4") (pin "B4") (pinfunction "IO_L4P_T0_35_B4") (pintype "bidirectional"))
    )
    (net (code "44") (name "/C2") (class "Default")
      (node (ref "U4") (pin "C4") (pinfunction "IO_L12N_T1_MRCC_35_C4") (pintype "bidirectional"))
    )
    (net (code "45") (name "/C3") (class "Default")
      (node (ref "U4") (pin "B5") (pinfunction "IO_L2N_T0_AD12N_35_B5") (pintype "bidirectional"))
    )
    (net (code "46") (name "/C4") (class "Default")
      (node (ref "U4") (pin "E1") (pinfunction "IO_L15N_T2_DQS_35_E1") (pintype "bidirectional"))
    )
    (net (code "47") (name "/C6") (class "Default")
      (node (ref "U4") (pin "E5") (pinfunction "IO_L13N_T2_MRCC_35_E5") (pintype "bidirectional"))
    )
    (net (code "48") (name "/C7") (class "Default")
      (node (ref "U4") (pin "B6") (pinfunction "IO_L2P_T0_AD12P_35_B6") (pintype "bidirectional"))
    )
    (net (code "49") (name "/CKE") (class "Default")
      (node (ref "U4") (pin "F13") (pinfunction "IO_L16N_T2_A27_15_F13") (pintype "bidirectional"))
    )
    (net (code "50") (name "/CK_N") (class "Default")
      (node (ref "U4") (pin "C9") (pinfunction "IO_L1N_T0_AD0N_15_C9") (pintype "bidirectional"))
    )
    (net (code "51") (name "/CK_P") (class "Default")
      (node (ref "U4") (pin "C8") (pinfunction "IO_L1P_T0_AD0P_15_C8") (pintype "bidirectional"))
    )
    (net (code "52") (name "/CONFIG_TCK") (class "Default")
      (node (ref "R19") (pin "8") (pinfunction "8_8") (pintype "passive"))
    )
    (net (code "53") (name "/CONFIG_TCK_T") (class "Default")
      (node (ref "R19") (pin "1") (pinfunction "1_1") (pintype "passive"))
      (node (ref "U4") (pin "N7") (pinfunction "TDI_0_N7") (pintype "input"))
    )
    (net (code "54") (name "/CONFIG_TDI") (class "Default")
      (node (ref "R19") (pin "6") (pinfunction "6_6") (pintype "passive"))
    )
    (net (code "55") (name "/CONFIG_TDI_T") (class "Default")
      (node (ref "R19") (pin "3") (pinfunction "3_3") (pintype "passive"))
      (node (ref "U4") (pin "L7") (pinfunction "TCK_0_L7") (pintype "input"))
    )
    (net (code "56") (name "/CONFIG_TDO") (class "Default")
      (node (ref "U4") (pin "N8") (pinfunction "TDO_0_N8") (pintype "output"))
    )
    (net (code "57") (name "/CONFIG_TMS") (class "Default")
      (node (ref "R19") (pin "7") (pinfunction "7_7") (pintype "passive"))
    )
    (net (code "58") (name "/CONFIG_TMS_T") (class "Default")
      (node (ref "R19") (pin "2") (pinfunction "2_2") (pintype "passive"))
      (node (ref "U4") (pin "M7") (pinfunction "TMS_0_M7") (pintype "input"))
    )
    (net (code "59") (name "/D1") (class "Default")
      (node (ref "U4") (pin "B1") (pinfunction "IO_L9N_T1_DQS_AD7N_35_B1") (pintype "bidirectional"))
    )
    (net (code "60") (name "/D3") (class "Default")
      (node (ref "U4") (pin "A2") (pinfunction "IO_L8N_T1_AD14N_35_A2") (pintype "bidirectional"))
    )
    (net (code "61") (name "/D4") (class "Default")
      (node (ref "U4") (pin "E2") (pinfunction "IO_L10P_T1_AD15P_35_E2") (pintype "bidirectional"))
    )
    (net (code "62") (name "/D5") (class "Default")
      (node (ref "U4") (pin "A5") (pinfunction "IO_L3P_T0_DQS_AD5P_35_A5") (pintype "bidirectional"))
    )
    (net (code "63") (name "/D6") (class "Default")
      (node (ref "U4") (pin "A7") (pinfunction "IO_L1N_T0_AD4N_35_A7") (pintype "bidirectional"))
    )
    (net (code "64") (name "/DONE") (class "Default")
      (node (ref "R14") (pin "1") (pinfunction "1_1") (pintype "passive"))
      (node (ref "R15") (pin "1") (pinfunction "1_1") (pintype "passive"))
      (node (ref "U4") (pin "H10") (pinfunction "DONE_0_H10") (pintype "bidirectional"))
    )
    (net (code "65") (name "/DQ0") (class "Default")
      (node (ref "U4") (pin "G15") (pinfunction "IO_L24N_T3_RS0_15_G15") (pintype "bidirectional"))
    )
    (net (code "66") (name "/DQ1") (class "Default")
      (node (ref "U4") (pin "D14") (pinfunction "IO_L15P_T2_DQS_15_D14") (pintype "bidirectional"))
    )
    (net (code "67") (name "/DQ2") (class "Default")
      (node (ref "U4") (pin "G16") (pinfunction "IO_L22N_T3_A16_15_G16") (pintype "bidirectional"))
    )
    (net (code "68") (name "/DQ3") (class "Default")
      (node (ref "U4") (pin "F15") (pinfunction "IO_L18P_T2_A24_15_F15") (pintype "bidirectional"))
    )
    (net (code "69") (name "/DQ4") (class "Default")
      (node (ref "U4") (pin "H16") (pinfunction "IO_L22P_T3_A17_15_H16") (pintype "bidirectional"))
    )
    (net (code "70") (name "/DQ5") (class "Default")
      (node (ref "U4") (pin "J16") (pinfunction "IO_L23N_T3_FWE_B_15_J16") (pintype "bidirectional"))
    )
    (net (code "71") (name "/DQ6") (class "Default")
      (node (ref "U4") (pin "H14") (pinfunction "IO_L24P_T3_RS1_15_H14") (pintype "bidirectional"))
    )
    (net (code "72") (name "/DQ7") (class "Default")
      (node (ref "U4") (pin "J15") (pinfunction "IO_L23P_T3_FOE_B_15_J15") (pintype "bidirectional"))
    )
    (net (code "73") (name "/DQ8") (class "Default")
      (node (ref "U4") (pin "C16") (pinfunction "IO_L10P_T1_AD11P_15_C16") (pintype "bidirectional"))
    )
    (net (code "74") (name "/DQ9") (class "Default")
      (node (ref "U4") (pin "E16") (pinfunction "IO_L17P_T2_A26_15_E16") (pintype "bidirectional"))
    )
    (net (code "75") (name "/DQ10") (class "Default")
      (node (ref "U4") (pin "B16") (pinfunction "IO_L10N_T1_AD11N_15_B16") (pintype "bidirectional"))
    )
    (net (code "76") (name "/DQ11") (class "Default")
      (node (ref "U4") (pin "E15") (pinfunction "IO_L18N_T2_A23_15_E15") (pintype "bidirectional"))
    )
    (net (code "77") (name "/DQ12") (class "Default")
      (node (ref "U4") (pin "A15") (pinfunction "IO_L9N_T1_DQS_AD3N_15_A15") (pintype "bidirectional"))
    )
    (net (code "78") (name "/DQ13") (class "Default")
      (node (ref "U4") (pin "D16") (pinfunction "IO_L17N_T2_A25_15_D16") (pintype "bidirectional"))
    )
    (net (code "79") (name "/DQ14") (class "Default")
      (node (ref "U4") (pin "B15") (pinfunction "IO_L9P_T1_DQS_AD3P_15_B15") (pintype "bidirectional"))
    )
    (net (code "80") (name "/DQ15") (class "Default")
      (node (ref "U4") (pin "D15") (pinfunction "IO_L15N_T2_DQS_ADV_B_15_D15") (pintype "bidirectional"))
    )
    (net (code "82") (name "/E1") (class "Default")
      (node (ref "U4") (pin "D1") (pinfunction "IO_L10N_T1_AD15N_35_D1") (pintype "bidirectional"))
    )
    (net (code "83") (name "/E2") (class "Default")
      (node (ref "U4") (pin "B2") (pinfunction "IO_L8P_T1_AD14P_35_B2") (pintype "bidirectional"))
    )
    (net (code "84") (name "/E3") (class "Default")
      (node (ref "U4") (pin "C3") (pinfunction "IO_L7P_T1_AD6P_35_C3") (pintype "bidirectional"))
    )
    (net (code "85") (name "/E5") (class "Default")
      (node (ref "U4") (pin "C2") (pinfunction "IO_L7N_T1_AD6N_35_C2") (pintype "bidirectional"))
    )
    (net (code "86") (name "/E6") (class "Default")
      (node (ref "U4") (pin "H5") (pinfunction "IO_L18P_T2_35_H5") (pintype "bidirectional"))
    )
    (net (code "87") (name "/F2") (class "Default")
      (node (ref "U4") (pin "C1") (pinfunction "IO_L9P_T1_DQS_AD7P_35_C1") (pintype "bidirectional"))
    )
    (net (code "88") (name "/F3") (class "Default")
      (node (ref "U4") (pin "F2") (pinfunction "IO_L15P_T2_DQS_35_F2") (pintype "bidirectional"))
    )
    (net (code "89") (name "/F4") (class "Default")
      (node (ref "U4") (pin "F3") (pinfunction "IO_L14N_T2_SRCC_35_F3") (pintype "bidirectional"))
    )
    (net (code "90") (name "/F5") (class "Default")
      (node (ref "U4") (pin "E3") (pinfunction "IO_L11P_T1_SRCC_35_E3") (pintype "bidirectional"))
    )
    (net (code "91") (name "/G1") (class "Default")
      (node (ref "U4") (pin "H3") (pinfunction "IO_L21N_T3_DQS_35_H3") (pintype "bidirectional"))
    )
    (net (code "92") (name "/G2") (class "Default")
      (node (ref "U4") (pin "H2") (pinfunction "IO_L20P_T3_35_H2") (pintype "bidirectional"))
    )
    (net (code "93") (name "/G4") (class "Default")
      (node (ref "U4") (pin "G1") (pinfunction "IO_L17N_T2_35_G1") (pintype "bidirectional"))
    )
    (net (code "94") (name "/G5") (class "Default")
      (node (ref "U4") (pin "H4") (pinfunction "IO_L18N_T2_35_H4") (pintype "bidirectional"))
    )
    (net (code "95") (name "/H1") (class "Default")
      (node (ref "U4") (pin "J4") (pinfunction "IO_L19N_T3_VREF_35_J4") (pintype "bidirectional"))
    )
    (net (code "96") (name "/H2") (class "Default")
      (node (ref "U4") (pin "J3") (pinfunction "IO_L21P_T3_DQS_35_J3") (pintype "bidirectional"))
    )
    (net (code "97") (name "/H3") (class "Default")
      (node (ref "U4") (pin "L2") (pinfunction "IO_L23N_T3_35_L2") (pintype "bidirectional"))
    )
    (net (code "98") (name "/H4") (class "Default")
      (node (ref "U4") (pin "L3") (pinfunction "IO_L23P_T3_35_L3") (pintype "bidirectional"))
    )
    (net (code "99") (name "/H5") (class "Default")
      (node (ref "U4") (pin "K3") (pinfunction "IO_L24P_T3_35_K3") (pintype "bidirectional"))
    )
    (net (code "100") (name "/IN_Filter_ADC_N") (class "Default")
      (node (ref "R21") (pin "2") (pinfunction "2_2") (pintype "passive"))
    )
    (net (code "101") (name "/IN_Filter_ADC_P") (class "Default")
      (node (ref "R20") (pin "2") (pinfunction "2_2") (pintype "passive"))
    )
    (net (code "102") (name "/J1") (class "Default")
      (node (ref "U4") (pin "J5") (pinfunction "IO_L19P_T3_35_J5") (pintype "bidirectional"))
    )
    (net (code "103") (name "/J3") (class "Default")
      (node (ref "U4") (pin "K2") (pinfunction "IO_L24N_T3_35_K2") (pintype "bidirectional"))
    )
    (net (code "104") (name "/J4") (class "Default")
      (node (ref "U4") (pin "J1") (pinfunction "IO_L22N_T3_35_J1") (pintype "bidirectional"))
    )
    (net (code "105") (name "/J5") (class "Default")
      (node (ref "U4") (pin "H1") (pinfunction "IO_L20N_T3_35_H1") (pintype "bidirectional"))
    )
    (net (code "106") (name "/K1") (class "Default")
      (node (ref "U4") (pin "K5") (pinfunction "IO_25_35_K5") (pintype "bidirectional"))
    )
    (net (code "107") (name "/K2") (class "Default")
      (node (ref "U4") (pin "E6") (pinfunction "IO_0_35_E6") (pintype "bidirectional"))
    )
    (net (code "108") (name "/K3") (class "Default")
      (node (ref "U4") (pin "G4") (pinfunction "IO_L16N_T2_35_G4") (pintype "bidirectional"))
    )
    (net (code "109") (name "/K5") (class "Default")
      (node (ref "U4") (pin "G5") (pinfunction "IO_L16P_T2_35_G5") (pintype "bidirectional"))
    )
    (net (code "110") (name "/K13") (class "Default")
      (node (ref "U4") (pin "N6") (pinfunction "IO_L19N_T3_A09_D25_VREF_14_N6") (pintype "bidirectional"))
    )
    (net (code "111") (name "/L1_N") (class "Default")
      (node (ref "U4") (pin "P1") (pinfunction "IO_L4N_T0_34_P1") (pintype "bidirectional"))
    )
    (net (code "112") (name "/L1_P") (class "Default")
      (node (ref "U4") (pin "N1") (pinfunction "IO_L4P_T0_34_N1") (pintype "bidirectional"))
    )
    (net (code "113") (name "/L2") (class "Default")
      (node (ref "U4") (pin "G2") (pinfunction "IO_L17P_T2_35_G2") (pintype "bidirectional"))
    )
    (net (code "114") (name "/L2_N") (class "Default")
      (node (ref "U4") (pin "M4") (pinfunction "IO_L1N_T0_34_M4") (pintype "bidirectional"))
    )
    (net (code "115") (name "/L2_P") (class "Default")
      (node (ref "U4") (pin "L4") (pinfunction "IO_L1P_T0_34_L4") (pintype "bidirectional"))
    )
    (net (code "116") (name "/L3") (class "Default")
      (node (ref "U4") (pin "K1") (pinfunction "IO_L22P_T3_35_K1") (pintype "bidirectional"))
    )
    (net (code "117") (name "/L3_N") (class "Default")
      (node (ref "U4") (pin "R1") (pinfunction "IO_L7N_T1_34_R1") (pintype "bidirectional"))
    )
    (net (code "118") (name "/L3_P") (class "Default")
      (node (ref "U4") (pin "R2") (pinfunction "IO_L7P_T1_34_R2") (pintype "bidirectional"))
    )
    (net (code "119") (name "/L4_N") (class "Default")
      (node (ref "U4") (pin "M1") (pinfunction "IO_L2N_T0_34_M1") (pintype "bidirectional"))
    )
    (net (code "120") (name "/L4_P") (class "Default")
      (node (ref "U4") (pin "M2") (pinfunction "IO_L2P_T0_34_M2") (pintype "bidirectional"))
    )
    (net (code "121") (name "/L5") (class "Default")
      (node (ref "U4") (pin "L5") (pinfunction "IO_0_34_L5") (pintype "bidirectional"))
    )
    (net (code "122") (name "/L5_N") (class "Default")
      (node (ref "U4") (pin "T2") (pinfunction "IO_L8N_T1_34_T2") (pintype "bidirectional"))
    )
    (net (code "123") (name "/L5_P") (class "Default")
      (node (ref "U4") (pin "R3") (pinfunction "IO_L8P_T1_34_R3") (pintype "bidirectional"))
    )
    (net (code "124") (name "/L6_N") (class "Default")
      (node (ref "U4") (pin "N2") (pinfunction "IO_L3N_T0_DQS_34_N2") (pintype "bidirectional"))
    )
    (net (code "125") (name "/L6_P") (class "Default")
      (node (ref "U4") (pin "N3") (pinfunction "IO_L3P_T0_DQS_34_N3") (pintype "bidirectional"))
    )
    (net (code "126") (name "/L7_N") (class "Default")
      (node (ref "U4") (pin "T3") (pinfunction "IO_L9N_T1_DQS_34_T3") (pintype "bidirectional"))
    )
    (net (code "127") (name "/L7_P") (class "Default")
      (node (ref "U4") (pin "T4") (pinfunction "IO_L9P_T1_DQS_34_T4") (pintype "bidirectional"))
    )
    (net (code "128") (name "/L8_N") (class "Default")
      (node (ref "U4") (pin "P3") (pinfunction "IO_L5N_T0_34_P3") (pintype "bidirectional"))
    )
    (net (code "129") (name "/L8_P") (class "Default")
      (node (ref "U4") (pin "P4") (pinfunction "IO_L5P_T0_34_P4") (pintype "bidirectional"))
    )
    (net (code "130") (name "/L9_N") (class "Default")
      (node (ref "U4") (pin "N4") (pinfunction "IO_L6N_T0_VREF_34_N4") (pintype "bidirectional"))
    )
    (net (code "131") (name "/L9_P") (class "Default")
      (node (ref "U4") (pin "M5") (pinfunction "IO_L6P_T0_34_M5") (pintype "bidirectional"))
    )
    (net (code "132") (name "/L13") (class "Default")
      (node (ref "U4") (pin "M14") (pinfunction "IO_L4N_T0_D05_14_M14") (pintype "bidirectional"))
    )
    (net (code "133") (name "/LDM") (class "Default")
      (node (ref "U4") (pin "C11") (pinfunction "IO_L11P_T1_SRCC_15_C11") (pintype "bidirectional"))
    )
    (net (code "134") (name "/LDQS_N") (class "Default")
      (node (ref "U4") (pin "A8") (pinfunction "IO_L2P_T0_AD8P_15_A8") (pintype "bidirectional"))
    )
    (net (code "135") (name "/LDQS_P") (class "Default")
      (node (ref "U4") (pin "A9") (pinfunction "IO_L2N_T0_AD8N_15_A9") (pintype "bidirectional"))
    )
    (net (code "136") (name "/LED0") (class "Default")
      (node (ref "U4") (pin "T15") (pinfunction "IO_L10N_T1_D15_14_T15") (pintype "bidirectional"))
    )
    (net (code "137") (name "/LED1") (class "Default")
      (node (ref "U4") (pin "R15") (pinfunction "IO_L9P_T1_DQS_14_R15") (pintype "bidirectional"))
    )
    (net (code "138") (name "/LED2") (class "Default")
      (node (ref "U4") (pin "R16") (pinfunction "IO_L9N_T1_DQS_D13_14_R16") (pintype "bidirectional"))
    )
    (net (code "139") (name "/LED3") (class "Default")
      (node (ref "U4") (pin "P15") (pinfunction "IO_L8P_T1_D11_14_P15") (pintype "bidirectional"))
    )
    (net (code "140") (name "/LED4") (class "Default")
      (node (ref "U4") (pin "P16") (pinfunction "IO_L8N_T1_D12_14_P16") (pintype "bidirectional"))
    )
    (net (code "141") (name "/LED5") (class "Default")
      (node (ref "U4") (pin "N16") (pinfunction "IO_L7N_T1_D10_14_N16") (pintype "bidirectional"))
    )
    (net (code "142") (name "/LED6") (class "Default")
      (node (ref "U4") (pin "M15") (pinfunction "IO_L3N_T0_DQS_EMCCLK_14_M15") (pintype "bidirectional"))
    )
    (net (code "143") (name "/LED7") (class "Default")
      (node (ref "U4") (pin "M16") (pinfunction "IO_L7P_T1_D09_14_M16") (pintype "bidirectional"))
    )
    (net (code "144") (name "/M6") (class "Default")
      (node (ref "U4") (pin "L14") (pinfunction "IO_L4P_T0_D04_14_L14") (pintype "bidirectional"))
    )
    (net (code "145") (name "/M15") (class "Default")
      (node (ref "U4") (pin "P8") (pinfunction "IO_L20P_T3_A08_D24_14_P8") (pintype "bidirectional"))
    )
    (net (code "146") (name "/N6") (class "Default")
      (node (ref "U4") (pin "M12") (pinfunction "IO_L6N_T0_D08_VREF_14_M12") (pintype "bidirectional"))
    )
    (net (code "147") (name "/N9") (class "Default")
      (node (ref "U4") (pin "T9") (pinfunction "IO_L22P_T3_A05_D21_14_T9") (pintype "bidirectional"))
    )
    (net (code "148") (name "/N11") (class "Default")
      (node (ref "U4") (pin "P11") (pinfunction "IO_L14N_T2_SRCC_14_P11") (pintype "bidirectional"))
    )
    (net (code "149") (name "/N12") (class "Default")
      (node (ref "U4") (pin "N12") (pinfunction "IO_L13N_T2_MRCC_14_N12") (pintype "bidirectional"))
    )
    (net (code "150") (name "/N13") (class "Default")
      (node (ref "U4") (pin "P9") (pinfunction "IO_L18N_T2_A11_D27_14_P9") (pintype "bidirectional"))
    )
    (net (code "151") (name "/ODT") (class "Default")
      (node (ref "U4") (pin "D11") (pinfunction "IO_L14N_T2_SRCC_15_D11") (pintype "bidirectional"))
    )
    (net (code "152") (name "/P5") (class "Default")
      (node (ref "U4") (pin "P5") (pinfunction "IO_L10P_T1_34_P5") (pintype "bidirectional"))
    )
    (net (code "153") (name "/P8") (class "Default")
      (node (ref "U4") (pin "T8") (pinfunction "IO_L21N_T3_DQS_A06_D22_14_T8") (pintype "bidirectional"))
    )
    (net (code "154") (name "/P9") (class "Default")
      (node (ref "U4") (pin "R8") (pinfunction "IO_L20N_T3_A07_D23_14_R8") (pintype "bidirectional"))
    )
    (net (code "155") (name "/P10") (class "Default")
      (node (ref "U4") (pin "R10") (pinfunction "IO_L17P_T2_A14_D30_14_R10") (pintype "bidirectional"))
    )
    (net (code "156") (name "/P11") (class "Default")
      (node (ref "U4") (pin "T12") (pinfunction "IO_L15N_T2_DQS_DOUT_CSO_B_14_T12") (pintype "bidirectional"))
    )
    (net (code "157") (name "/P13") (class "Default")
      (node (ref "U4") (pin "N9") (pinfunction "IO_L18P_T2_A12_D28_14_N9") (pintype "bidirectional"))
    )
    (net (code "158") (name "/P14") (class "Default")
      (node (ref "U4") (pin "T10") (pinfunction "IO_L22N_T3_A04_D20_14_T10") (pintype "bidirectional"))
    )
    (net (code "159") (name "/PROGRAM_B") (class "Default")
      (node (ref "R18") (pin "1") (pinfunction "1_1") (pintype "passive"))
      (node (ref "U4") (pin "L9") (pinfunction "PROGRAM_B_0_L9") (pintype "input"))
    )
    (net (code "160") (name "/QSPI_CLK") (class "Default")
      (node (ref "U4") (pin "E8") (pinfunction "CCLK_0_E8") (pintype "bidirectional"))
    )
    (net (code "161") (name "/QSPI_DATA0") (class "Default")
      (node (ref "R16") (pin "5") (pinfunction "5_5") (pintype "passive"))
    )
    (net (code "162") (name "/QSPI_DATA0_T") (class "Default")
      (node (ref "R16") (pin "4") (pinfunction "4_4") (pintype "passive"))
      (node (ref "U4") (pin "K16") (pinfunction "IO_L2N_T0_D03_14_K16") (pintype "bidirectional"))
    )
    (net (code "163") (name "/QSPI_DATA1") (class "Default")
      (node (ref "R16") (pin "7") (pinfunction "7_7") (pintype "passive"))
    )
    (net (code "164") (name "/QSPI_DATA1_T") (class "Default")
      (node (ref "R16") (pin "2") (pinfunction "2_2") (pintype "passive"))
      (node (ref "U4") (pin "J14") (pinfunction "IO_L1N_T0_D01_DIN_14_J14") (pintype "bidirectional"))
    )
    (net (code "165") (name "/QSPI_DATA2") (class "Default")
      (node (ref "R16") (pin "6") (pinfunction "6_6") (pintype "passive"))
    )
    (net (code "166") (name "/QSPI_DATA2_T") (class "Default")
      (node (ref "R16") (pin "3") (pinfunction "3_3") (pintype "passive"))
      (node (ref "U4") (pin "K15") (pinfunction "IO_L2P_T0_D02_14_K15") (pintype "bidirectional"))
    )
    (net (code "167") (name "/QSPI_DATA3") (class "Default")
      (node (ref "R16") (pin "8") (pinfunction "8_8") (pintype "passive"))
    )
    (net (code "168") (name "/QSPI_DATA3_T") (class "Default")
      (node (ref "R16") (pin "1") (pinfunction "1_1") (pintype "passive"))
      (node (ref "U4") (pin "J13") (pinfunction "IO_L1P_T0_D00_MOSI_14_J13") (pintype "bidirectional"))
    )
    (net (code "169") (name "/QSPI_~{CS}") (class "Default")
      (node (ref "U4") (pin "L12") (pinfunction "IO_L6P_T0_FCS_B_14_L12") (pintype "bidirectional"))
    )
    (net (code "170") (name "/R7") (class "Default")
      (node (ref "U4") (pin "T5") (pinfunction "IO_L23N_T3_A02_D18_14_T5") (pintype "bidirectional"))
    )
    (net (code "171") (name "/R8") (class "Default")
      (node (ref "U4") (pin "T7") (pinfunction "IO_L21P_T3_DQS_14_T7") (pintype "bidirectional"))
    )
    (net (code "172") (name "/R10") (class "Default")
      (node (ref "U4") (pin "N13") (pinfunction "IO_L11P_T1_SRCC_14_N13") (pintype "bidirectional"))
    )
    (net (code "173") (name "/R11") (class "Default")
      (node (ref "U4") (pin "N14") (pinfunction "IO_L12P_T1_MRCC_14_N14") (pintype "bidirectional"))
    )
    (net (code "174") (name "/R12") (class "Default")
      (node (ref "U4") (pin "P14") (pinfunction "IO_L12N_T1_MRCC_14_P14") (pintype "bidirectional"))
    )
    (net (code "175") (name "/R13") (class "Default")
      (node (ref "U4") (pin "R11") (pinfunction "IO_L17N_T2_A13_D29_14_R11") (pintype "bidirectional"))
    )
    (net (code "176") (name "/R15") (class "Default")
      (node (ref "U4") (pin "T13") (pinfunction "IO_L16N_T2_A15_D31_14_T13") (pintype "bidirectional"))
    )
    (net (code "177") (name "/R16") (class "Default")
      (node (ref "U4") (pin "R12") (pinfunction "IO_L15P_T2_DQS_RDWR_B_14_R12") (pintype "bidirectional"))
    )
    (net (code "178") (name "/RESET") (class "Default")
      (node (ref "U4") (pin "R5") (pinfunction "IO_L23P_T3_A03_D19_14_R5") (pintype "bidirectional"))
    )
    (net (code "179") (name "/T5") (class "Default")
      (node (ref "U4") (pin "K13") (pinfunction "IO_L5P_T0_D06_14_K13") (pintype "bidirectional"))
    )
    (net (code "180") (name "/T7") (class "Default")
      (node (ref "U4") (pin "K12") (pinfunction "IO_0_14_K12") (pintype "bidirectional"))
    )
    (net (code "181") (name "/T8") (class "Default")
      (node (ref "U4") (pin "L13") (pinfunction "IO_L5N_T0_D07_14_L13") (pintype "bidirectional"))
    )
    (net (code "182") (name "/T9") (class "Default")
      (node (ref "U4") (pin "R7") (pinfunction "IO_L24N_T3_A00_D16_14_R7") (pintype "bidirectional"))
    )
    (net (code "183") (name "/T10") (class "Default")
      (node (ref "U4") (pin "M6") (pinfunction "IO_L19P_T3_A10_D26_14_M6") (pintype "bidirectional"))
    )
    (net (code "184") (name "/T12") (class "Default")
      (node (ref "U4") (pin "P13") (pinfunction "IO_L11N_T1_SRCC_14_P13") (pintype "bidirectional"))
    )
    (net (code "185") (name "/T13") (class "Default")
      (node (ref "U4") (pin "P10") (pinfunction "IO_L14P_T2_SRCC_14_P10") (pintype "bidirectional"))
    )
    (net (code "186") (name "/T14") (class "Default")
      (node (ref "U4") (pin "T14") (pinfunction "IO_L10P_T1_D14_14_T14") (pintype "bidirectional"))
    )
    (net (code "187") (name "/T15") (class "Default")
      (node (ref "U4") (pin "R13") (pinfunction "IO_L16P_T2_CSI_B_14_R13") (pintype "bidirectional"))
    )
    (net (code "188") (name "/UART_RX") (class "Default")
      (node (ref "U4") (pin "P6") (pinfunction "IO_25_14_P6") (pintype "bidirectional"))
    )
    (net (code "189") (name "/UART_TX") (class "Default")
      (node (ref "U4") (pin "R6") (pinfunction "IO_L24P_T3_A01_D17_14_R6") (pintype "bidirectional"))
    )
    (net (code "190") (name "/UDM") (class "Default")
      (node (ref "U4") (pin "B10") (pinfunction "IO_L4P_T0_15_B10") (pintype "bidirectional"))
    )
    (net (code "191") (name "/UDQS_N") (class "Default")
      (node (ref "U4") (pin "D9") (pinfunction "IO_L6N_T0_VREF_15_D9") (pintype "bidirectional"))
    )
    (net (code "192") (name "/UDQS_P") (class "Default")
      (node (ref "U4") (pin "D8") (pinfunction "IO_L6P_T0_15_D8") (pintype "bidirectional"))
    )
    (net (code "193") (name "/~{CAS}") (class "Default")
      (node (ref "U4") (pin "C12") (pinfunction "IO_L11N_T1_SRCC_15_C12") (pintype "bidirectional"))
    )
    (net (code "194") (name "/~{CS}") (class "Default")
      (node (ref "U4") (pin "D10") (pinfunction "IO_0_15_D10") (pintype "bidirectional"))
    )
    (net (code "195") (name "/~{DDR_RESET}") (class "Default")
      (node (ref "U4") (pin "F12") (pinfunction "IO_L16P_T2_A28_15_F12") (pintype "bidirectional"))
    )
    (net (code "196") (name "/~{RAS}") (class "Default")
      (node (ref "U4") (pin "A13") (pinfunction "IO_L7P_T1_AD2P_15_A13") (pintype "bidirectional"))
    )
    (net (code "197") (name "/~{WE}") (class "Default")
      (node (ref "U4") (pin "D13") (pinfunction "IO_L12P_T1_MRCC_15_D13") (pintype "bidirectional"))
    )
    (net (code "198") (name "AGND") (class "Default")
      (node (ref "C37") (pin "1") (pinfunction "1_1") (pintype "passive"))
      (node (ref "C52") (pin "1") (pinfunction "1_1") (pintype "passive"))
      (node (ref "C53") (pin "1") (pinfunction "1_1") (pintype "passive"))
      (node (ref "C54") (pin "1") (pinfunction "1_1") (pintype "passive"))
      (node (ref "L4") (pin "2") (pinfunction "2_2") (pintype "passive"))
      (node (ref "U4") (pin "G7") (pinfunction "GNDADC_0_G7") (pintype "power_in"))
      (node (ref "U4") (pin "H7") (pinfunction "VREFN_0_H7") (pintype "power_in"))
      (node (ref "U5") (pin "3") (pinfunction "GND_3") (pintype "passive"))
    )
    (net (code "199") (name "GND") (class "Default")
      (node (ref "C21") (pin "1") (pinfunction "1_1") (pintype "passive"))
      (node (ref "C22") (pin "1") (pinfunction "1_1") (pintype "passive"))
      (node (ref "C23") (pin "1") (pinfunction "1_1") (pintype "passive"))
      (node (ref "C24") (pin "1") (pinfunction "1_1") (pintype "passive"))
      (node (ref "C25") (pin "1") (pinfunction "1_1") (pintype "passive"))
      (node (ref "C26") (pin "1") (pinfunction "1_1") (pintype "passive"))
      (node (ref "C27") (pin "1") (pinfunction "1_1") (pintype "passive"))
      (node (ref "C28") (pin "1") (pinfunction "1_1") (pintype "passive"))
      (node (ref "C29") (pin "1") (pinfunction "1_1") (pintype "passive"))
      (node (ref "C30") (pin "1") (pinfunction "1_1") (pintype "passive"))
      (node (ref "C31") (pin "1") (pinfunction "1_1") (pintype "passive"))
      (node (ref "C32") (pin "1") (pinfunction "1_1") (pintype "passive"))
      (node (ref "C33") (pin "1") (pinfunction "1_1") (pintype "passive"))
      (node (ref "C34") (pin "1") (pinfunction "1_1") (pintype "passive"))
      (node (ref "C35") (pin "1") (pinfunction "1_1") (pintype "passive"))
      (node (ref "C36") (pin "1") (pinfunction "1_1") (pintype "passive"))
      (node (ref "C38") (pin "1") (pinfunction "1_1") (pintype "passive"))
      (node (ref "C39") (pin "1") (pinfunction "1_1") (pintype "passive"))
      (node (ref "C40") (pin "1") (pinfunction "1_1") (pintype "passive"))
      (node (ref "C41") (pin "1") (pinfunction "1_1") (pintype "passive"))
      (node (ref "C42") (pin "1") (pinfunction "1_1") (pintype "passive"))
      (node (ref "C43") (pin "1") (pinfunction "1_1") (pintype "passive"))
      (node (ref "C44") (pin "1") (pinfunction "1_1") (pintype "passive"))
      (node (ref "C46") (pin "1") (pinfunction "1_1") (pintype "passive"))
      (node (ref "C47") (pin "1") (pinfunction "1_1") (pintype "passive"))
      (node (ref "C48") (pin "1") (pinfunction "1_1") (pintype "passive"))
      (node (ref "C50") (pin "1") (pinfunction "1_1") (pintype "passive"))
      (node (ref "C51") (pin "1") (pinfunction "1_1") (pintype "passive"))
      (node (ref "C56") (pin "1") (pinfunction "1_1") (pintype "passive"))
      (node (ref "C57") (pin "1") (pinfunction "1_1") (pintype "passive"))
      (node (ref "C58") (pin "1") (pinfunction "1_1") (pintype "passive"))
      (node (ref "C59") (pin "1") (pinfunction "1_1") (pintype "passive"))
      (node (ref "C60") (pin "1") (pinfunction "1_1") (pintype "passive"))
      (node (ref "C61") (pin "1") (pinfunction "1_1") (pintype "passive"))
      (node (ref "C62") (pin "1") (pinfunction "1_1") (pintype "passive"))
      (node (ref "C63") (pin "1") (pinfunction "1_1") (pintype "passive"))
      (node (ref "C64") (pin "1") (pinfunction "1_1") (pintype "passive"))
      (node (ref "C65") (pin "1") (pinfunction "1_1") (pintype "passive"))
      (node (ref "C66") (pin "1") (pinfunction "1_1") (pintype "passive"))
      (node (ref "C67") (pin "1") (pinfunction "1_1") (pintype "passive"))
      (node (ref "C68") (pin "1") (pinfunction "1_1") (pintype "passive"))
      (node (ref "C69") (pin "1") (pinfunction "1_1") (pintype "passive"))
      (node (ref "D3") (pin "C") (pinfunction "C_C") (pintype "passive"))
      (node (ref "L4") (pin "1") (pinfunction "1_1") (pintype "passive"))
      (node (ref "U4") (pin "A1") (pinfunction "GND_A1") (pintype "power_in"))
      (node (ref "U4") (pin "A11") (pinfunction "GND_A11") (pintype "power_in"))
      (node (ref "U4") (pin "B8") (pinfunction "GND_B8") (pintype "power_in"))
      (node (ref "U4") (pin "C15") (pinfunction "GND_C15") (pintype "power_in"))
      (node (ref "U4") (pin "C5") (pinfunction "GND_C5") (pintype "power_in"))
      (node (ref "U4") (pin "D12") (pinfunction "GND_D12") (pintype "power_in"))
      (node (ref "U4") (pin "D2") (pinfunction "GND_D2") (pintype "power_in"))
      (node (ref "U4") (pin "E9") (pinfunction "GND_E9") (pintype "power_in"))
      (node (ref "U4") (pin "F10") (pinfunction "GND_F10") (pintype "power_in"))
      (node (ref "U4") (pin "F16") (pinfunction "GND_F16") (pintype "power_in"))
      (node (ref "U4") (pin "F6") (pinfunction "GND_F6") (pintype "power_in"))
      (node (ref "U4") (pin "F8") (pinfunction "VCCBATT_0_F8") (pintype "power_in"))
      (node (ref "U4") (pin "G13") (pinfunction "GND_G13") (pintype "power_in"))
      (node (ref "U4") (pin "G3") (pinfunction "GND_G3") (pintype "power_in"))
      (node (ref "U4") (pin "G9") (pinfunction "GND_G9") (pintype "power_in"))
      (node (ref "U4") (pin "H6") (pinfunction "GND_H6") (pintype "power_in"))
      (node (ref "U4") (pin "J11") (pinfunction "GND_J11") (pintype "power_in"))
      (node (ref "U4") (pin "J9") (pinfunction "GND_J9") (pintype "power_in"))
      (node (ref "U4") (pin "K14") (pinfunction "GND_K14") (pintype "power_in"))
      (node (ref "U4") (pin "K4") (pinfunction "GND_K4") (pintype "power_in"))
      (node (ref "U4") (pin "K6") (pinfunction "GND_K6") (pintype "power_in"))
      (node (ref "U4") (pin "K7") (pinfunction "DXN_0_K7") (pintype "input"))
      (node (ref "U4") (pin "K8") (pinfunction "DXP_0_K8") (pintype "input"))
      (node (ref "U4") (pin "L1") (pinfunction "GND_L1") (pintype "power_in"))
      (node (ref "U4") (pin "L11") (pinfunction "GND_L11") (pintype "power_in"))
      (node (ref "U4") (pin "M10") (pinfunction "M1_0_M10") (pintype "input"))
      (node (ref "U4") (pin "M11") (pinfunction "M2_0_M11") (pintype "input"))
      (node (ref "U4") (pin "M8") (pinfunction "GND_M8") (pintype "power_in"))
      (node (ref "U4") (pin "N15") (pinfunction "GND_N15") (pintype "power_in"))
      (node (ref "U4") (pin "N5") (pinfunction "GND_N5") (pintype "power_in"))
      (node (ref "U4") (pin "P12") (pinfunction "GND_P12") (pintype "power_in"))
      (node (ref "U4") (pin "P2") (pinfunction "GND_P2") (pintype "power_in"))
      (node (ref "U4") (pin "R9") (pinfunction "GND_R9") (pintype "power_in"))
      (node (ref "U4") (pin "T16") (pinfunction "GND_T16") (pintype "power_in"))
      (node (ref "U4") (pin "T6") (pinfunction "GND_T6") (pintype "power_in"))
      (node (ref "XTAL2") (pin "2") (pinfunction "GND_2") (pintype "power_in"))
    )
    (net (code "200") (name "Net-(D3-PadA)") (class "Default")
      (node (ref "D3") (pin "A") (pinfunction "A_A") (pintype "passive"))
      (node (ref "R15") (pin "2") (pinfunction "2_2") (pintype "passive"))
    )
    (net (code "201") (name "Net-(U4G-INIT_B_0)") (class "Default")
      (node (ref "R17") (pin "1") (pinfunction "1_1") (pintype "passive"))
      (node (ref "U4") (pin "K10") (pinfunction "INIT_B_0_K10") (pintype "bidirectional"))
    )
    (net (code "202") (name "unconnected-(R19-Pad4)") (class "Default")
      (node (ref "R19") (pin "4") (pinfunction "4_4") (pintype "passive+no_connect"))
    )
    (net (code "203") (name "unconnected-(R19-Pad5)") (class "Default")
      (node (ref "R19") (pin "5") (pinfunction "5_5") (pintype "passive+no_connect"))
    )
    (net (code "204") (name "unconnected-(U4C-IO_L4N_T0_15-PadB11)") (class "Default")
      (node (ref "U4") (pin "B11") (pinfunction "IO_L4N_T0_15_B11") (pintype "bidirectional+no_connect"))
    )
  )
)
